# zilla1.net
KiCad netlist of a schematic drawn in EAGLE
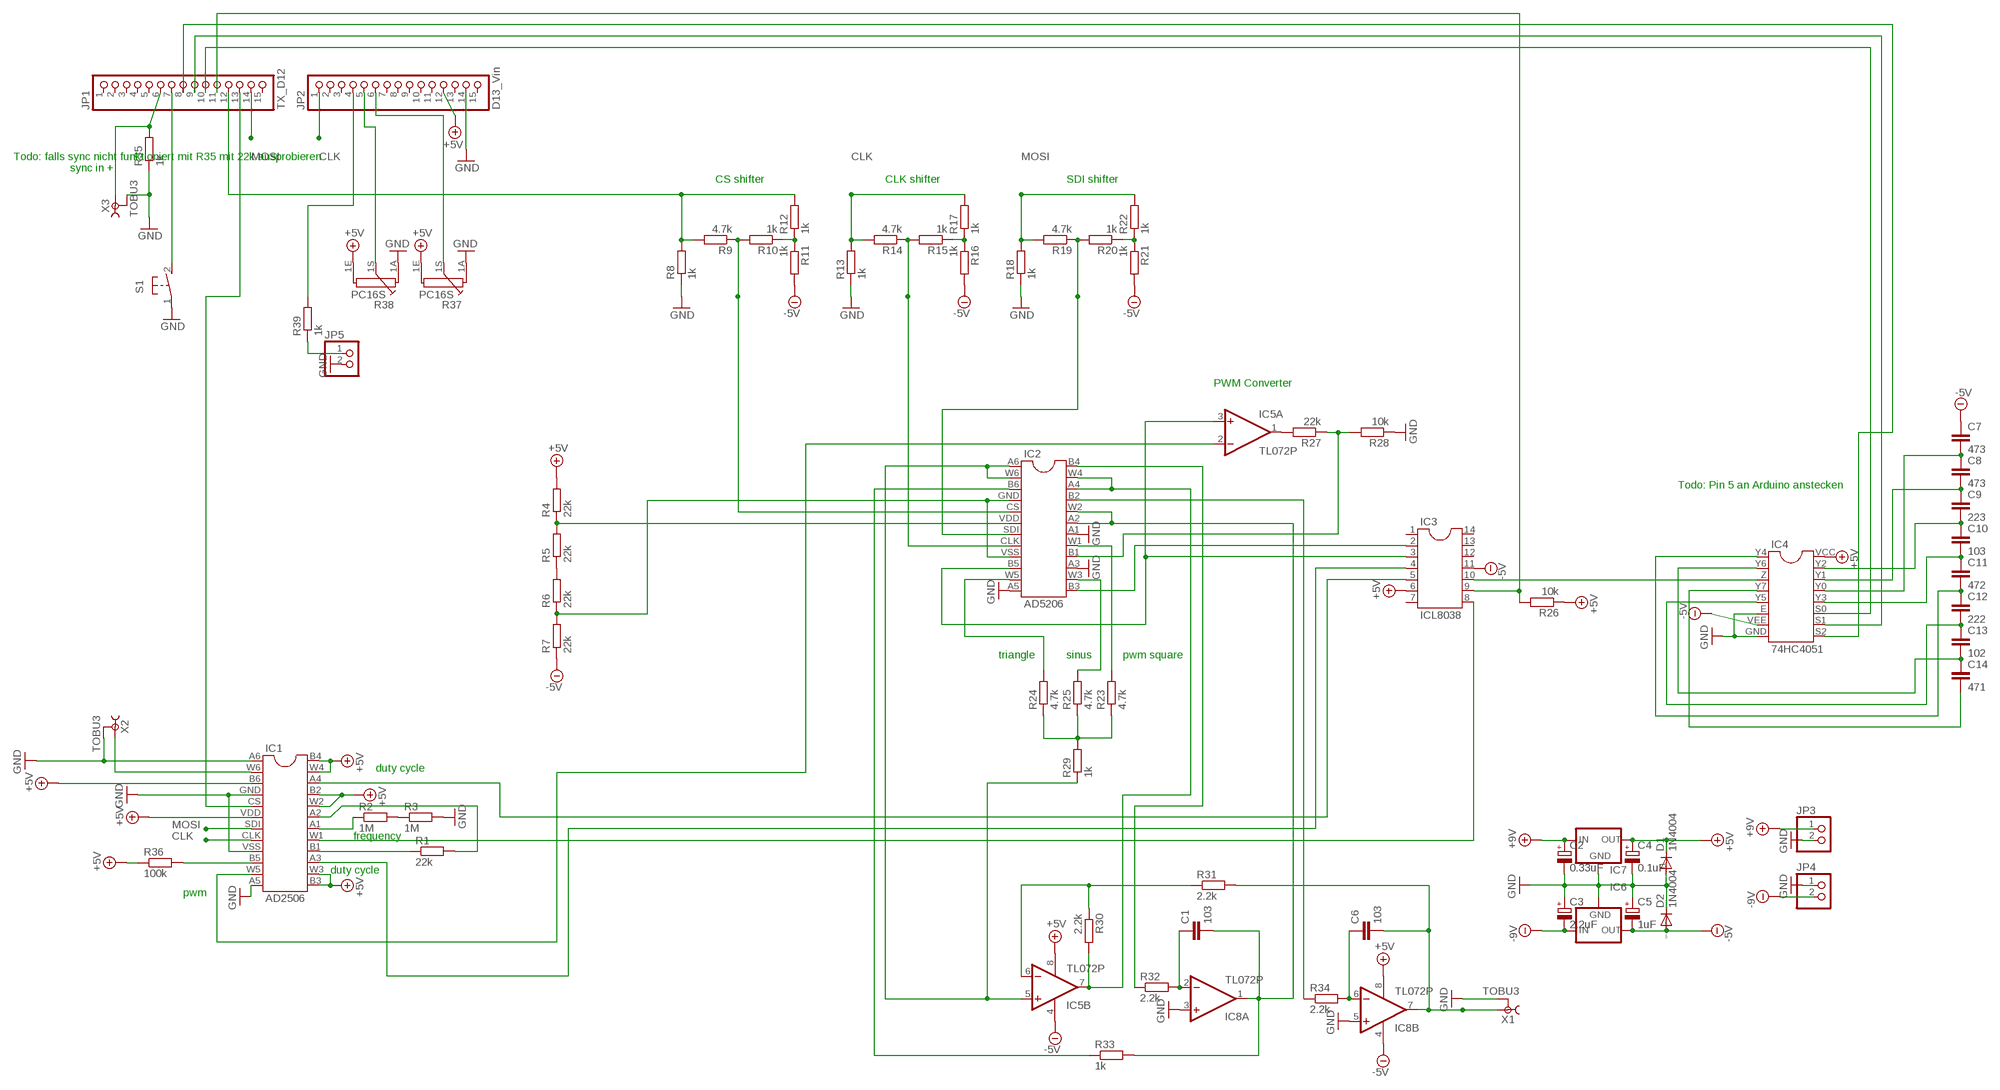
[diagram p0: schematic, sheet 1]

(export (version "E")
  (design (tool "Eeschema 10.0.6"))
  (components
    (comp (ref "C1")
      (value "103")
      (footprint "eagle-import:C025-024X044")
      (libsource (lib "eagle-import") (part "C-EU025-024X044"))
    )
    (comp (ref "C2")
      (value "0.33uF")
      (footprint "eagle-import:E2-5")
      (libsource (lib "eagle-import") (part "CPOL-EUE2-5"))
    )
    (comp (ref "C3")
      (value "2.2uF")
      (footprint "eagle-import:E2-5")
      (libsource (lib "eagle-import") (part "CPOL-EUE2-5"))
    )
    (comp (ref "C4")
      (value "0.1uF")
      (footprint "eagle-import:E2-5")
      (libsource (lib "eagle-import") (part "CPOL-EUE2-5"))
    )
    (comp (ref "C5")
      (value "1uF")
      (footprint "eagle-import:E2-5")
      (libsource (lib "eagle-import") (part "CPOL-EUE2-5"))
    )
    (comp (ref "C6")
      (value "103")
      (footprint "eagle-import:C025-024X044")
      (libsource (lib "eagle-import") (part "C-EU025-024X044"))
    )
    (comp (ref "C7")
      (value "473")
      (footprint "eagle-import:C025-024X044")
      (libsource (lib "eagle-import") (part "C-EU025-024X044"))
    )
    (comp (ref "C8")
      (value "473")
      (footprint "eagle-import:C025-024X044")
      (libsource (lib "eagle-import") (part "C-EU025-024X044"))
    )
    (comp (ref "C9")
      (value "223")
      (footprint "eagle-import:C025-024X044")
      (libsource (lib "eagle-import") (part "C-EU025-024X044"))
    )
    (comp (ref "C10")
      (value "103")
      (footprint "eagle-import:C025-024X044")
      (libsource (lib "eagle-import") (part "C-EU025-024X044"))
    )
    (comp (ref "C11")
      (value "472")
      (footprint "eagle-import:C025-024X044")
      (libsource (lib "eagle-import") (part "C-EU025-024X044"))
    )
    (comp (ref "C12")
      (value "222")
      (footprint "eagle-import:C025-024X044")
      (libsource (lib "eagle-import") (part "C-EU025-024X044"))
    )
    (comp (ref "C13")
      (value "102")
      (footprint "eagle-import:C025-024X044")
      (libsource (lib "eagle-import") (part "C-EU025-024X044"))
    )
    (comp (ref "C14")
      (value "471")
      (footprint "eagle-import:C025-024X044")
      (libsource (lib "eagle-import") (part "C-EU025-024X044"))
    )
    (comp (ref "D1")
      (value "1N4004")
      (footprint "eagle-import:DO41-10")
      (libsource (lib "eagle-import") (part "1N4004"))
    )
    (comp (ref "D2")
      (value "1N4004")
      (footprint "eagle-import:DO41-10")
      (libsource (lib "eagle-import") (part "1N4004"))
    )
    (comp (ref "IC1")
      (value "AD2506")
      (footprint "eagle-import:AD5206")
      (libsource (lib "eagle-import") (part "DIL24-3"))
    )
    (comp (ref "IC2")
      (value "AD5206")
      (footprint "eagle-import:AD5206")
      (libsource (lib "eagle-import") (part "DIL24-3"))
    )
    (comp (ref "IC3")
      (value "ICL8038")
      (footprint "eagle-import:DIL14")
      (libsource (lib "eagle-import") (part "DIL14"))
    )
    (comp (ref "IC4")
      (value "74HC4051")
      (footprint "eagle-import:DIL16")
      (libsource (lib "eagle-import") (part "DIL16"))
    )
    (comp (ref "IC5")
      (value "TL072P")
      (footprint "eagle-import:DIL08")
      (libsource (lib "eagle-import") (part "TL072P"))
    )
    (comp (ref "IC6")
      (value "79XXS")
      (footprint "eagle-import:79XXS")
      (libsource (lib "eagle-import") (part "79XXS"))
    )
    (comp (ref "IC7")
      (value "78XXS")
      (footprint "eagle-import:78XXS")
      (libsource (lib "eagle-import") (part "78XXS"))
    )
    (comp (ref "IC8")
      (value "TL072P")
      (footprint "eagle-import:DIL08")
      (libsource (lib "eagle-import") (part "TL072P"))
    )
    (comp (ref "JP1")
      (value "TX_D12")
      (footprint "eagle-import:1X15")
      (libsource (lib "eagle-import") (part "PINHD-1X15"))
    )
    (comp (ref "JP2")
      (value "D13_Vin")
      (footprint "eagle-import:1X15")
      (libsource (lib "eagle-import") (part "PINHD-1X15"))
    )
    (comp (ref "JP3")
      (value "PINHD-1X2")
      (footprint "eagle-import:1X02")
      (libsource (lib "eagle-import") (part "PINHD-1X2"))
    )
    (comp (ref "JP4")
      (value "PINHD-1X2")
      (footprint "eagle-import:1X02")
      (libsource (lib "eagle-import") (part "PINHD-1X2"))
    )
    (comp (ref "JP5")
      (value "PINHD-1X2")
      (footprint "eagle-import:1X02")
      (libsource (lib "eagle-import") (part "PINHD-1X2"))
    )
    (comp (ref "R1")
      (value "22k")
      (footprint "eagle-import:0207_7")
      (libsource (lib "eagle-import") (part "R-EU_0207/7"))
    )
    (comp (ref "R2")
      (value "1M")
      (footprint "eagle-import:0207_7")
      (libsource (lib "eagle-import") (part "R-EU_0207/7"))
    )
    (comp (ref "R3")
      (value "1M")
      (footprint "eagle-import:0207_7")
      (libsource (lib "eagle-import") (part "R-EU_0207/7"))
    )
    (comp (ref "R4")
      (value "22k")
      (footprint "eagle-import:0207_7")
      (libsource (lib "eagle-import") (part "R-EU_0207/7"))
    )
    (comp (ref "R5")
      (value "22k")
      (footprint "eagle-import:0207_7")
      (libsource (lib "eagle-import") (part "R-EU_0207/7"))
    )
    (comp (ref "R6")
      (value "22k")
      (footprint "eagle-import:0207_7")
      (libsource (lib "eagle-import") (part "R-EU_0207/7"))
    )
    (comp (ref "R7")
      (value "22k")
      (footprint "eagle-import:0207_7")
      (libsource (lib "eagle-import") (part "R-EU_0207/7"))
    )
    (comp (ref "R8")
      (value "1k")
      (footprint "eagle-import:0207_7")
      (libsource (lib "eagle-import") (part "R-EU_0207/7"))
    )
    (comp (ref "R9")
      (value "4.7k")
      (footprint "eagle-import:0207_7")
      (libsource (lib "eagle-import") (part "R-EU_0207/7"))
    )
    (comp (ref "R10")
      (value "1k")
      (footprint "eagle-import:0207_7")
      (libsource (lib "eagle-import") (part "R-EU_0207/7"))
    )
    (comp (ref "R11")
      (value "1k")
      (footprint "eagle-import:0207_7")
      (libsource (lib "eagle-import") (part "R-EU_0207/7"))
    )
    (comp (ref "R12")
      (value "1k")
      (footprint "eagle-import:0207_7")
      (libsource (lib "eagle-import") (part "R-EU_0207/7"))
    )
    (comp (ref "R13")
      (value "1k")
      (footprint "eagle-import:0207_7")
      (libsource (lib "eagle-import") (part "R-EU_0207/7"))
    )
    (comp (ref "R14")
      (value "4.7k")
      (footprint "eagle-import:0207_7")
      (libsource (lib "eagle-import") (part "R-EU_0207/7"))
    )
    (comp (ref "R15")
      (value "1k")
      (footprint "eagle-import:0207_7")
      (libsource (lib "eagle-import") (part "R-EU_0207/7"))
    )
    (comp (ref "R16")
      (value "1k")
      (footprint "eagle-import:0207_7")
      (libsource (lib "eagle-import") (part "R-EU_0207/7"))
    )
    (comp (ref "R17")
      (value "1k")
      (footprint "eagle-import:0207_7")
      (libsource (lib "eagle-import") (part "R-EU_0207/7"))
    )
    (comp (ref "R18")
      (value "1k")
      (footprint "eagle-import:0207_7")
      (libsource (lib "eagle-import") (part "R-EU_0207/7"))
    )
    (comp (ref "R19")
      (value "4.7k")
      (footprint "eagle-import:0207_7")
      (libsource (lib "eagle-import") (part "R-EU_0207/7"))
    )
    (comp (ref "R20")
      (value "1k")
      (footprint "eagle-import:0207_7")
      (libsource (lib "eagle-import") (part "R-EU_0207/7"))
    )
    (comp (ref "R21")
      (value "1k")
      (footprint "eagle-import:0207_7")
      (libsource (lib "eagle-import") (part "R-EU_0207/7"))
    )
    (comp (ref "R22")
      (value "1k")
      (footprint "eagle-import:0207_7")
      (libsource (lib "eagle-import") (part "R-EU_0207/7"))
    )
    (comp (ref "R23")
      (value "4.7k")
      (footprint "eagle-import:0207_7")
      (libsource (lib "eagle-import") (part "R-EU_0207/7"))
    )
    (comp (ref "R24")
      (value "4.7k")
      (footprint "eagle-import:0207_7")
      (libsource (lib "eagle-import") (part "R-EU_0207/7"))
    )
    (comp (ref "R25")
      (value "4.7k")
      (footprint "eagle-import:0207_7")
      (libsource (lib "eagle-import") (part "R-EU_0207/7"))
    )
    (comp (ref "R26")
      (value "10k")
      (footprint "eagle-import:0207_7")
      (libsource (lib "eagle-import") (part "R-EU_0207/7"))
    )
    (comp (ref "R27")
      (value "22k")
      (footprint "eagle-import:0207_7")
      (libsource (lib "eagle-import") (part "R-EU_0207/7"))
    )
    (comp (ref "R28")
      (value "10k")
      (footprint "eagle-import:0207_7")
      (libsource (lib "eagle-import") (part "R-EU_0207/7"))
    )
    (comp (ref "R29")
      (value "1k")
      (footprint "eagle-import:0207_7")
      (libsource (lib "eagle-import") (part "R-EU_0207/7"))
    )
    (comp (ref "R30")
      (value "2.2k")
      (footprint "eagle-import:0207_7")
      (libsource (lib "eagle-import") (part "R-EU_0207/7"))
    )
    (comp (ref "R31")
      (value "2.2k")
      (footprint "eagle-import:0207_7")
      (libsource (lib "eagle-import") (part "R-EU_0207/7"))
    )
    (comp (ref "R32")
      (value "2.2k")
      (footprint "eagle-import:0207_7")
      (libsource (lib "eagle-import") (part "R-EU_0207/7"))
    )
    (comp (ref "R33")
      (value "1k")
      (footprint "eagle-import:0207_7")
      (libsource (lib "eagle-import") (part "R-EU_0207/7"))
    )
    (comp (ref "R34")
      (value "2.2k")
      (footprint "eagle-import:0207_7")
      (libsource (lib "eagle-import") (part "R-EU_0207/7"))
    )
    (comp (ref "R35")
      (value "1k")
      (footprint "eagle-import:0207_7")
      (libsource (lib "eagle-import") (part "R-EU_0207/7"))
    )
    (comp (ref "R36")
      (value "100k")
      (footprint "eagle-import:0207_7")
      (libsource (lib "eagle-import") (part "R-EU_0207/7"))
    )
    (comp (ref "R37")
      (value "PC16S")
      (footprint "eagle-import:PC16S")
      (libsource (lib "eagle-import") (part "PC16S"))
    )
    (comp (ref "R38")
      (value "PC16S")
      (footprint "eagle-import:PC16S")
      (libsource (lib "eagle-import") (part "PC16S"))
    )
    (comp (ref "R39")
      (value "1k")
      (footprint "eagle-import:0207_7")
      (libsource (lib "eagle-import") (part "R-EU_0207/7"))
    )
    (comp (ref "S1")
      (value "31-XX")
      (footprint "eagle-import:B3F-31XX")
      (fields (field (name "MPN") "B3F-3100"))
      (libsource (lib "eagle-import") (part "31-XX"))
    )
    (comp (ref "X1")
      (value "TOBU3")
      (footprint "eagle-import:TOBU3")
      (fields (field (name "MF") "FARNELL") (field (name "MPN") "TOBU 3"))
      (libsource (lib "eagle-import") (part "TOBU3"))
    )
    (comp (ref "X2")
      (value "TOBU3")
      (footprint "eagle-import:TOBU3")
      (fields (field (name "MF") "FARNELL") (field (name "MPN") "TOBU 3"))
      (libsource (lib "eagle-import") (part "TOBU3"))
    )
    (comp (ref "X3")
      (value "TOBU3")
      (footprint "eagle-import:TOBU3")
      (fields (field (name "MF") "FARNELL") (field (name "MPN") "TOBU 3"))
      (libsource (lib "eagle-import") (part "TOBU3"))
    )
  )
  (nets
    (net (code "1") (name "+5V") (class "Default")
      (node (ref "C4") (pin "+") (pinfunction "+_+") (pintype "passive"))
      (node (ref "D1") (pin "C") (pinfunction "C_C") (pintype "passive"))
      (node (ref "IC1") (pin "B2") (pinfunction "21_B2") (pintype "passive"))
      (node (ref "IC1") (pin "B3") (pinfunction "13_B3") (pintype "passive"))
      (node (ref "IC1") (pin "B4") (pinfunction "24_B4") (pintype "passive"))
      (node (ref "IC1") (pin "B6") (pinfunction "3_B6") (pintype "passive"))
      (node (ref "IC1") (pin "VDD") (pinfunction "6_VDD") (pintype "passive"))
      (node (ref "IC1") (pin "W2") (pinfunction "20_W2") (pintype "passive"))
      (node (ref "IC1") (pin "W3") (pinfunction "14_W3") (pintype "passive"))
      (node (ref "IC1") (pin "W4") (pinfunction "23_W4") (pintype "passive"))
      (node (ref "IC3") (pin "6") (pinfunction "6_6") (pintype "passive"))
      (node (ref "IC4") (pin "VCC") (pinfunction "16_VCC") (pintype "passive"))
      (node (ref "IC5") (pin "8") (pinfunction "V+_8") (pintype "power_in"))
      (node (ref "IC7") (pin "OUT") (pinfunction "OUT_OUT") (pintype "passive"))
      (node (ref "IC8") (pin "8") (pinfunction "V+_8") (pintype "power_in"))
      (node (ref "JP2") (pin "12") (pinfunction "12_12") (pintype "passive"))
      (node (ref "R26") (pin "1") (pinfunction "1_1") (pintype "passive"))
      (node (ref "R36") (pin "1") (pinfunction "1_1") (pintype "passive"))
      (node (ref "R37") (pin "1E") (pinfunction "1E_1E") (pintype "passive"))
      (node (ref "R38") (pin "1E") (pinfunction "1E_1E") (pintype "passive"))
      (node (ref "R4") (pin "2") (pinfunction "2_2") (pintype "passive"))
    )
    (net (code "2") (name "+9V") (class "Default")
      (node (ref "C2") (pin "+") (pinfunction "+_+") (pintype "passive"))
      (node (ref "IC7") (pin "IN") (pinfunction "IN_IN") (pintype "input"))
      (node (ref "JP3") (pin "1") (pinfunction "1_1") (pintype "passive"))
    )
    (net (code "3") (name "-5V") (class "Default")
      (node (ref "C5") (pin "-") (pinfunction "-_-") (pintype "passive"))
      (node (ref "C7") (pin "1") (pinfunction "1_1") (pintype "passive"))
      (node (ref "D2") (pin "A") (pinfunction "A_A") (pintype "passive"))
      (node (ref "IC3") (pin "11") (pinfunction "11_11") (pintype "passive"))
      (node (ref "IC4") (pin "VEE") (pinfunction "7_VEE") (pintype "passive"))
      (node (ref "IC5") (pin "4") (pinfunction "V-_4") (pintype "power_in"))
      (node (ref "IC6") (pin "OUT") (pinfunction "OUT_OUT") (pintype "passive"))
      (node (ref "IC8") (pin "4") (pinfunction "V-_4") (pintype "power_in"))
      (node (ref "R11") (pin "2") (pinfunction "2_2") (pintype "passive"))
      (node (ref "R16") (pin "2") (pinfunction "2_2") (pintype "passive"))
      (node (ref "R21") (pin "2") (pinfunction "2_2") (pintype "passive"))
      (node (ref "R7") (pin "1") (pinfunction "1_1") (pintype "passive"))
    )
    (net (code "4") (name "-9V") (class "Default")
      (node (ref "C3") (pin "-") (pinfunction "-_-") (pintype "passive"))
      (node (ref "IC6") (pin "IN") (pinfunction "IN_IN") (pintype "input"))
      (node (ref "JP4") (pin "2") (pinfunction "2_2") (pintype "passive"))
    )
    (net (code "5") (name "/CLK") (class "Default")
      (node (ref "IC1") (pin "CLK") (pinfunction "8_CLK") (pintype "passive"))
      (node (ref "JP2") (pin "1") (pinfunction "1_1") (pintype "passive"))
      (node (ref "R13") (pin "2") (pinfunction "2_2") (pintype "passive"))
      (node (ref "R14") (pin "2") (pinfunction "2_2") (pintype "passive"))
      (node (ref "R17") (pin "2") (pinfunction "2_2") (pintype "passive"))
    )
    (net (code "6") (name "/MOSI") (class "Default")
      (node (ref "IC1") (pin "SDI") (pinfunction "7_SDI") (pintype "passive"))
      (node (ref "JP1") (pin "14") (pinfunction "14_14") (pintype "passive"))
      (node (ref "R18") (pin "2") (pinfunction "2_2") (pintype "passive"))
      (node (ref "R19") (pin "2") (pinfunction "2_2") (pintype "passive"))
      (node (ref "R22") (pin "2") (pinfunction "2_2") (pintype "passive"))
    )
    (net (code "7") (name "GND") (class "Default")
      (node (ref "C2") (pin "-") (pinfunction "-_-") (pintype "passive"))
      (node (ref "C3") (pin "+") (pinfunction "+_+") (pintype "passive"))
      (node (ref "C4") (pin "-") (pinfunction "-_-") (pintype "passive"))
      (node (ref "C5") (pin "+") (pinfunction "+_+") (pintype "passive"))
      (node (ref "D1") (pin "A") (pinfunction "A_A") (pintype "passive"))
      (node (ref "D2") (pin "C") (pinfunction "C_C") (pintype "passive"))
      (node (ref "IC1") (pin "A5") (pinfunction "12_A5") (pintype "passive"))
      (node (ref "IC1") (pin "A6") (pinfunction "TEST_A6") (pintype "passive"))
      (node (ref "IC1") (pin "GND") (pinfunction "4_GND") (pintype "passive"))
      (node (ref "IC1") (pin "VSS") (pinfunction "9_VSS") (pintype "passive"))
      (node (ref "IC2") (pin "A1") (pinfunction "18_A1") (pintype "passive"))
      (node (ref "IC2") (pin "A3") (pinfunction "15_A3") (pintype "passive"))
      (node (ref "IC2") (pin "A5") (pinfunction "12_A5") (pintype "passive"))
      (node (ref "IC4") (pin "E") (pinfunction "6_E") (pintype "passive"))
      (node (ref "IC4") (pin "GND") (pinfunction "8_GND") (pintype "passive"))
      (node (ref "IC6") (pin "GND") (pinfunction "GND_GND") (pintype "input"))
      (node (ref "IC7") (pin "GND") (pinfunction "GND_GND") (pintype "input"))
      (node (ref "IC8") (pin "3") (pinfunction "+IN_3") (pintype "input"))
      (node (ref "IC8") (pin "5") (pinfunction "+IN_5") (pintype "input"))
      (node (ref "JP2") (pin "14") (pinfunction "14_14") (pintype "passive"))
      (node (ref "JP3") (pin "2") (pinfunction "2_2") (pintype "passive"))
      (node (ref "JP4") (pin "1") (pinfunction "1_1") (pintype "passive"))
      (node (ref "JP5") (pin "2") (pinfunction "2_2") (pintype "passive"))
      (node (ref "R13") (pin "1") (pinfunction "1_1") (pintype "passive"))
      (node (ref "R18") (pin "1") (pinfunction "1_1") (pintype "passive"))
      (node (ref "R28") (pin "1") (pinfunction "1_1") (pintype "passive"))
      (node (ref "R3") (pin "2") (pinfunction "2_2") (pintype "passive"))
      (node (ref "R35") (pin "1") (pinfunction "1_1") (pintype "passive"))
      (node (ref "R37") (pin "1A") (pinfunction "1A_1A") (pintype "passive"))
      (node (ref "R38") (pin "1A") (pinfunction "1A_1A") (pintype "passive"))
      (node (ref "R8") (pin "1") (pinfunction "1_1") (pintype "passive"))
      (node (ref "S1") (pin "1") (pinfunction "P_1") (pintype "passive"))
      (node (ref "X1") (pin "2") (pinfunction "2_2") (pintype "passive"))
      (node (ref "X1") (pin "2@1") (pinfunction "2_2@1") (pintype "passive"))
      (node (ref "X1") (pin "2@2") (pinfunction "2_2@2") (pintype "passive"))
      (node (ref "X2") (pin "2") (pinfunction "2_2") (pintype "passive"))
      (node (ref "X2") (pin "2@1") (pinfunction "2_2@1") (pintype "passive"))
      (node (ref "X2") (pin "2@2") (pinfunction "2_2@2") (pintype "passive"))
      (node (ref "X3") (pin "2") (pinfunction "2_2") (pintype "passive"))
      (node (ref "X3") (pin "2@1") (pinfunction "2_2@1") (pintype "passive"))
      (node (ref "X3") (pin "2@2") (pinfunction "2_2@2") (pintype "passive"))
    )
    (net (code "8") (name "Net-(IC1-5)") (class "Default")
      (node (ref "IC1") (pin "CS") (pinfunction "5_CS") (pintype "passive"))
      (node (ref "JP1") (pin "13") (pinfunction "13_13") (pintype "passive"))
    )
    (net (code "9") (name "Net-(IC1-10)") (class "Default")
      (node (ref "IC1") (pin "B5") (pinfunction "10_B5") (pintype "passive"))
      (node (ref "R36") (pin "2") (pinfunction "2_2") (pintype "passive"))
    )
    (net (code "10") (name "Net-(IC1-11)") (class "Default")
      (node (ref "IC1") (pin "W5") (pinfunction "11_W5") (pintype "passive"))
      (node (ref "IC5") (pin "2") (pinfunction "-IN_2") (pintype "input"))
    )
    (net (code "11") (name "Net-(IC1-15)") (class "Default")
      (node (ref "IC1") (pin "A3") (pinfunction "15_A3") (pintype "passive"))
      (node (ref "IC3") (pin "4") (pinfunction "4_4") (pintype "passive"))
    )
    (net (code "12") (name "Net-(IC1-16)") (class "Default")
      (node (ref "IC1") (pin "B1") (pinfunction "16_B1") (pintype "passive"))
      (node (ref "R1") (pin "1") (pinfunction "1_1") (pintype "passive"))
    )
    (net (code "13") (name "Net-(IC1-17)") (class "Default")
      (node (ref "IC1") (pin "W1") (pinfunction "17_W1") (pintype "passive"))
      (node (ref "IC3") (pin "8") (pinfunction "8_8") (pintype "passive"))
    )
    (net (code "14") (name "Net-(IC1-18)") (class "Default")
      (node (ref "IC1") (pin "A1") (pinfunction "18_A1") (pintype "passive"))
      (node (ref "R2") (pin "1") (pinfunction "1_1") (pintype "passive"))
    )
    (net (code "15") (name "Net-(IC1-19)") (class "Default")
      (node (ref "IC1") (pin "A2") (pinfunction "19_A2") (pintype "passive"))
      (node (ref "R1") (pin "2") (pinfunction "2_2") (pintype "passive"))
    )
    (net (code "16") (name "Net-(IC1-22)") (class "Default")
      (node (ref "IC1") (pin "A4") (pinfunction "22_A4") (pintype "passive"))
      (node (ref "IC3") (pin "5") (pinfunction "5_5") (pintype "passive"))
    )
    (net (code "17") (name "Net-(IC1-VCC)") (class "Default")
      (node (ref "IC1") (pin "W6") (pinfunction "VCC_W6") (pintype "passive"))
      (node (ref "X2") (pin "1") (pinfunction "1_1") (pintype "passive"))
    )
    (net (code "18") (name "Net-(IC2-3)") (class "Default")
      (node (ref "IC2") (pin "B6") (pinfunction "3_B6") (pintype "passive"))
      (node (ref "R33") (pin "1") (pinfunction "1_1") (pintype "passive"))
    )
    (net (code "19") (name "Net-(IC2-4)") (class "Default")
      (node (ref "IC2") (pin "GND") (pinfunction "4_GND") (pintype "passive"))
      (node (ref "IC2") (pin "VSS") (pinfunction "9_VSS") (pintype "passive"))
      (node (ref "R6") (pin "1") (pinfunction "1_1") (pintype "passive"))
      (node (ref "R7") (pin "2") (pinfunction "2_2") (pintype "passive"))
    )
    (net (code "20") (name "Net-(IC2-5)") (class "Default")
      (node (ref "IC2") (pin "CS") (pinfunction "5_CS") (pintype "passive"))
      (node (ref "R10") (pin "2") (pinfunction "2_2") (pintype "passive"))
      (node (ref "R9") (pin "1") (pinfunction "1_1") (pintype "passive"))
    )
    (net (code "21") (name "Net-(IC2-6)") (class "Default")
      (node (ref "IC2") (pin "VDD") (pinfunction "6_VDD") (pintype "passive"))
      (node (ref "R4") (pin "1") (pinfunction "1_1") (pintype "passive"))
      (node (ref "R5") (pin "2") (pinfunction "2_2") (pintype "passive"))
    )
    (net (code "22") (name "Net-(IC2-7)") (class "Default")
      (node (ref "IC2") (pin "SDI") (pinfunction "7_SDI") (pintype "passive"))
      (node (ref "R19") (pin "1") (pinfunction "1_1") (pintype "passive"))
      (node (ref "R20") (pin "2") (pinfunction "2_2") (pintype "passive"))
    )
    (net (code "23") (name "Net-(IC2-8)") (class "Default")
      (node (ref "IC2") (pin "CLK") (pinfunction "8_CLK") (pintype "passive"))
      (node (ref "R14") (pin "1") (pinfunction "1_1") (pintype "passive"))
      (node (ref "R15") (pin "2") (pinfunction "2_2") (pintype "passive"))
    )
    (net (code "24") (name "Net-(IC2-10)") (class "Default")
      (node (ref "IC2") (pin "B5") (pinfunction "10_B5") (pintype "passive"))
      (node (ref "IC3") (pin "3") (pinfunction "3_3") (pintype "passive"))
      (node (ref "IC5") (pin "3") (pinfunction "+IN_3") (pintype "input"))
    )
    (net (code "25") (name "Net-(IC2-11)") (class "Default")
      (node (ref "IC2") (pin "W5") (pinfunction "11_W5") (pintype "passive"))
      (node (ref "R24") (pin "2") (pinfunction "2_2") (pintype "passive"))
    )
    (net (code "26") (name "Net-(IC2-13)") (class "Default")
      (node (ref "IC2") (pin "B3") (pinfunction "13_B3") (pintype "passive"))
      (node (ref "IC3") (pin "2") (pinfunction "2_2") (pintype "passive"))
    )
    (net (code "27") (name "Net-(IC2-14)") (class "Default")
      (node (ref "IC2") (pin "W3") (pinfunction "14_W3") (pintype "passive"))
      (node (ref "R25") (pin "2") (pinfunction "2_2") (pintype "passive"))
    )
    (net (code "28") (name "Net-(IC2-16)") (class "Default")
      (node (ref "IC2") (pin "B1") (pinfunction "16_B1") (pintype "passive"))
      (node (ref "R27") (pin "1") (pinfunction "1_1") (pintype "passive"))
      (node (ref "R28") (pin "2") (pinfunction "2_2") (pintype "passive"))
    )
    (net (code "29") (name "Net-(IC2-17)") (class "Default")
      (node (ref "IC2") (pin "W1") (pinfunction "17_W1") (pintype "passive"))
      (node (ref "R23") (pin "2") (pinfunction "2_2") (pintype "passive"))
    )
    (net (code "30") (name "Net-(IC2-19)") (class "Default")
      (node (ref "C1") (pin "2") (pinfunction "2_2") (pintype "passive"))
      (node (ref "IC2") (pin "A2") (pinfunction "19_A2") (pintype "passive"))
      (node (ref "IC2") (pin "W2") (pinfunction "20_W2") (pintype "passive"))
      (node (ref "IC8") (pin "1") (pinfunction "OUT_1") (pintype "output"))
      (node (ref "R33") (pin "2") (pinfunction "2_2") (pintype "passive"))
    )
    (net (code "31") (name "Net-(IC2-21)") (class "Default")
      (node (ref "IC2") (pin "B2") (pinfunction "21_B2") (pintype "passive"))
      (node (ref "R34") (pin "1") (pinfunction "1_1") (pintype "passive"))
    )
    (net (code "32") (name "Net-(IC2-22)") (class "Default")
      (node (ref "IC2") (pin "A4") (pinfunction "22_A4") (pintype "passive"))
      (node (ref "IC2") (pin "W4") (pinfunction "23_W4") (pintype "passive"))
      (node (ref "IC5") (pin "7") (pinfunction "OUT_7") (pintype "output"))
      (node (ref "R30") (pin "2") (pinfunction "2_2") (pintype "passive"))
    )
    (net (code "33") (name "Net-(IC2-24)") (class "Default")
      (node (ref "IC2") (pin "B4") (pinfunction "24_B4") (pintype "passive"))
      (node (ref "R32") (pin "1") (pinfunction "1_1") (pintype "passive"))
    )
    (net (code "34") (name "Net-(IC2-TEST)") (class "Default")
      (node (ref "IC2") (pin "A6") (pinfunction "TEST_A6") (pintype "passive"))
      (node (ref "IC2") (pin "W6") (pinfunction "VCC_W6") (pintype "passive"))
      (node (ref "IC5") (pin "5") (pinfunction "+IN_5") (pintype "input"))
      (node (ref "R29") (pin "1") (pinfunction "1_1") (pintype "passive"))
    )
    (net (code "35") (name "Net-(IC3-Pad9)") (class "Default")
      (node (ref "IC3") (pin "9") (pinfunction "9_9") (pintype "passive"))
      (node (ref "JP1") (pin "11") (pinfunction "11_11") (pintype "passive"))
      (node (ref "R26") (pin "2") (pinfunction "2_2") (pintype "passive"))
    )
    (net (code "36") (name "Net-(IC4-1)") (class "Default")
      (node (ref "C11") (pin "2") (pinfunction "2_2") (pintype "passive"))
      (node (ref "C12") (pin "1") (pinfunction "1_1") (pintype "passive"))
      (node (ref "IC4") (pin "Y4") (pinfunction "1_Y4") (pintype "passive"))
    )
    (net (code "37") (name "Net-(IC4-2)") (class "Default")
      (node (ref "C13") (pin "2") (pinfunction "2_2") (pintype "passive"))
      (node (ref "C14") (pin "1") (pinfunction "1_1") (pintype "passive"))
      (node (ref "IC4") (pin "Y6") (pinfunction "2_Y6") (pintype "passive"))
    )
    (net (code "38") (name "Net-(IC4-3)") (class "Default")
      (node (ref "IC3") (pin "10") (pinfunction "10_10") (pintype "passive"))
      (node (ref "IC4") (pin "Z") (pinfunction "3_Z") (pintype "passive"))
    )
    (net (code "39") (name "Net-(IC4-4)") (class "Default")
      (node (ref "C14") (pin "2") (pinfunction "2_2") (pintype "passive"))
      (node (ref "IC4") (pin "Y7") (pinfunction "4_Y7") (pintype "passive"))
    )
    (net (code "40") (name "Net-(IC4-5)") (class "Default")
      (node (ref "C12") (pin "2") (pinfunction "2_2") (pintype "passive"))
      (node (ref "C13") (pin "1") (pinfunction "1_1") (pintype "passive"))
      (node (ref "IC4") (pin "Y5") (pinfunction "5_Y5") (pintype "passive"))
    )
    (net (code "41") (name "Net-(IC4-9)") (class "Default")
      (node (ref "IC4") (pin "S2") (pinfunction "9_S2") (pintype "passive"))
      (node (ref "JP1") (pin "8") (pinfunction "8_8") (pintype "passive"))
    )
    (net (code "42") (name "Net-(IC4-10)") (class "Default")
      (node (ref "IC4") (pin "S1") (pinfunction "10_S1") (pintype "passive"))
      (node (ref "JP1") (pin "9") (pinfunction "9_9") (pintype "passive"))
    )
    (net (code "43") (name "Net-(IC4-11)") (class "Default")
      (node (ref "IC4") (pin "S0") (pinfunction "11_S0") (pintype "passive"))
      (node (ref "JP1") (pin "10") (pinfunction "10_10") (pintype "passive"))
    )
    (net (code "44") (name "Net-(IC4-12)") (class "Default")
      (node (ref "C10") (pin "2") (pinfunction "2_2") (pintype "passive"))
      (node (ref "C11") (pin "1") (pinfunction "1_1") (pintype "passive"))
      (node (ref "IC4") (pin "Y3") (pinfunction "12_Y3") (pintype "passive"))
    )
    (net (code "45") (name "Net-(IC4-13)") (class "Default")
      (node (ref "C7") (pin "2") (pinfunction "2_2") (pintype "passive"))
      (node (ref "C8") (pin "1") (pinfunction "1_1") (pintype "passive"))
      (node (ref "IC4") (pin "Y0") (pinfunction "13_Y0") (pintype "passive"))
    )
    (net (code "46") (name "Net-(IC4-14)") (class "Default")
      (node (ref "C8") (pin "2") (pinfunction "2_2") (pintype "passive"))
      (node (ref "C9") (pin "1") (pinfunction "1_1") (pintype "passive"))
      (node (ref "IC4") (pin "Y1") (pinfunction "14_Y1") (pintype "passive"))
    )
    (net (code "47") (name "Net-(IC4-15)") (class "Default")
      (node (ref "C10") (pin "1") (pinfunction "1_1") (pintype "passive"))
      (node (ref "C9") (pin "2") (pinfunction "2_2") (pintype "passive"))
      (node (ref "IC4") (pin "Y2") (pinfunction "15_Y2") (pintype "passive"))
    )
    (net (code "48") (name "Net-(IC5A-OUT)") (class "Default")
      (node (ref "IC5") (pin "1") (pinfunction "OUT_1") (pintype "output"))
      (node (ref "R27") (pin "2") (pinfunction "2_2") (pintype "passive"))
    )
    (net (code "49") (name "Net-(IC5B--IN)") (class "Default")
      (node (ref "IC5") (pin "6") (pinfunction "-IN_6") (pintype "input"))
      (node (ref "R30") (pin "1") (pinfunction "1_1") (pintype "passive"))
      (node (ref "R31") (pin "1") (pinfunction "1_1") (pintype "passive"))
    )
    (net (code "50") (name "Net-(IC8A--IN)") (class "Default")
      (node (ref "C1") (pin "1") (pinfunction "1_1") (pintype "passive"))
      (node (ref "IC8") (pin "2") (pinfunction "-IN_2") (pintype "input"))
      (node (ref "R32") (pin "2") (pinfunction "2_2") (pintype "passive"))
    )
    (net (code "51") (name "Net-(IC8B--IN)") (class "Default")
      (node (ref "C6") (pin "1") (pinfunction "1_1") (pintype "passive"))
      (node (ref "IC8") (pin "6") (pinfunction "-IN_6") (pintype "input"))
      (node (ref "R34") (pin "2") (pinfunction "2_2") (pintype "passive"))
    )
    (net (code "52") (name "Net-(IC8B-OUT)") (class "Default")
      (node (ref "C6") (pin "2") (pinfunction "2_2") (pintype "passive"))
      (node (ref "IC8") (pin "7") (pinfunction "OUT_7") (pintype "output"))
      (node (ref "R31") (pin "2") (pinfunction "2_2") (pintype "passive"))
      (node (ref "X1") (pin "1") (pinfunction "1_1") (pintype "passive"))
    )
    (net (code "53") (name "Net-(JP1-Pad6)") (class "Default")
      (node (ref "JP1") (pin "6") (pinfunction "6_6") (pintype "passive"))
      (node (ref "R35") (pin "2") (pinfunction "2_2") (pintype "passive"))
      (node (ref "X3") (pin "1") (pinfunction "1_1") (pintype "passive"))
    )
    (net (code "54") (name "Net-(JP1-Pad12)") (class "Default")
      (node (ref "JP1") (pin "12") (pinfunction "12_12") (pintype "passive"))
      (node (ref "R12") (pin "2") (pinfunction "2_2") (pintype "passive"))
      (node (ref "R8") (pin "2") (pinfunction "2_2") (pintype "passive"))
      (node (ref "R9") (pin "2") (pinfunction "2_2") (pintype "passive"))
    )
    (net (code "55") (name "Net-(JP2-Pad4)") (class "Default")
      (node (ref "JP2") (pin "4") (pinfunction "4_4") (pintype "passive"))
      (node (ref "R39") (pin "2") (pinfunction "2_2") (pintype "passive"))
    )
    (net (code "56") (name "Net-(JP2-Pad5)") (class "Default")
      (node (ref "JP2") (pin "5") (pinfunction "5_5") (pintype "passive"))
      (node (ref "R38") (pin "1S") (pinfunction "1S_1S") (pintype "passive"))
    )
    (net (code "57") (name "Net-(JP2-Pad6)") (class "Default")
      (node (ref "JP2") (pin "6") (pinfunction "6_6") (pintype "passive"))
      (node (ref "R37") (pin "1S") (pinfunction "1S_1S") (pintype "passive"))
    )
    (net (code "58") (name "Net-(JP5-Pad1)") (class "Default")
      (node (ref "JP5") (pin "1") (pinfunction "1_1") (pintype "passive"))
      (node (ref "R39") (pin "1") (pinfunction "1_1") (pintype "passive"))
    )
    (net (code "59") (name "Net-(R2-Pad2)") (class "Default")
      (node (ref "R2") (pin "2") (pinfunction "2_2") (pintype "passive"))
      (node (ref "R3") (pin "1") (pinfunction "1_1") (pintype "passive"))
    )
    (net (code "60") (name "Net-(R5-Pad1)") (class "Default")
      (node (ref "R5") (pin "1") (pinfunction "1_1") (pintype "passive"))
      (node (ref "R6") (pin "2") (pinfunction "2_2") (pintype "passive"))
    )
    (net (code "61") (name "Net-(R10-Pad1)") (class "Default")
      (node (ref "R10") (pin "1") (pinfunction "1_1") (pintype "passive"))
      (node (ref "R11") (pin "1") (pinfunction "1_1") (pintype "passive"))
      (node (ref "R12") (pin "1") (pinfunction "1_1") (pintype "passive"))
    )
    (net (code "62") (name "Net-(R15-Pad1)") (class "Default")
      (node (ref "R15") (pin "1") (pinfunction "1_1") (pintype "passive"))
      (node (ref "R16") (pin "1") (pinfunction "1_1") (pintype "passive"))
      (node (ref "R17") (pin "1") (pinfunction "1_1") (pintype "passive"))
    )
    (net (code "63") (name "Net-(R20-Pad1)") (class "Default")
      (node (ref "R20") (pin "1") (pinfunction "1_1") (pintype "passive"))
      (node (ref "R21") (pin "1") (pinfunction "1_1") (pintype "passive"))
      (node (ref "R22") (pin "1") (pinfunction "1_1") (pintype "passive"))
    )
    (net (code "64") (name "Net-(R23-Pad1)") (class "Default")
      (node (ref "R23") (pin "1") (pinfunction "1_1") (pintype "passive"))
      (node (ref "R24") (pin "1") (pinfunction "1_1") (pintype "passive"))
      (node (ref "R25") (pin "1") (pinfunction "1_1") (pintype "passive"))
      (node (ref "R29") (pin "2") (pinfunction "2_2") (pintype "passive"))
    )
    (net (code "65") (name "Net-(S1-S)") (class "Default")
      (node (ref "JP1") (pin "7") (pinfunction "7_7") (pintype "passive"))
      (node (ref "S1") (pin "2") (pinfunction "S_2") (pintype "passive"))
    )
    (net (code "66") (name "unconnected-(IC3-Pad1)") (class "Default")
      (node (ref "IC3") (pin "1") (pinfunction "1_1") (pintype "passive"))
    )
    (net (code "67") (name "unconnected-(IC3-Pad7)") (class "Default")
      (node (ref "IC3") (pin "7") (pinfunction "7_7") (pintype "passive"))
    )
    (net (code "68") (name "unconnected-(IC3-Pad12)") (class "Default")
      (node (ref "IC3") (pin "12") (pinfunction "12_12") (pintype "passive"))
    )
    (net (code "69") (name "unconnected-(IC3-Pad13)") (class "Default")
      (node (ref "IC3") (pin "13") (pinfunction "13_13") (pintype "passive"))
    )
    (net (code "70") (name "unconnected-(IC3-Pad14)") (class "Default")
      (node (ref "IC3") (pin "14") (pinfunction "14_14") (pintype "passive"))
    )
    (net (code "71") (name "unconnected-(JP1-Pad1)") (class "Default")
      (node (ref "JP1") (pin "1") (pinfunction "1_1") (pintype "passive"))
    )
    (net (code "72") (name "unconnected-(JP1-Pad2)") (class "Default")
      (node (ref "JP1") (pin "2") (pinfunction "2_2") (pintype "passive"))
    )
    (net (code "73") (name "unconnected-(JP1-Pad3)") (class "Default")
      (node (ref "JP1") (pin "3") (pinfunction "3_3") (pintype "passive"))
    )
    (net (code "74") (name "unconnected-(JP1-Pad4)") (class "Default")
      (node (ref "JP1") (pin "4") (pinfunction "4_4") (pintype "passive"))
    )
    (net (code "75") (name "unconnected-(JP1-Pad5)") (class "Default")
      (node (ref "JP1") (pin "5") (pinfunction "5_5") (pintype "passive"))
    )
    (net (code "76") (name "unconnected-(JP1-Pad15)") (class "Default")
      (node (ref "JP1") (pin "15") (pinfunction "15_15") (pintype "passive"))
    )
    (net (code "77") (name "unconnected-(JP2-Pad2)") (class "Default")
      (node (ref "JP2") (pin "2") (pinfunction "2_2") (pintype "passive"))
    )
    (net (code "78") (name "unconnected-(JP2-Pad3)") (class "Default")
      (node (ref "JP2") (pin "3") (pinfunction "3_3") (pintype "passive"))
    )
    (net (code "79") (name "unconnected-(JP2-Pad7)") (class "Default")
      (node (ref "JP2") (pin "7") (pinfunction "7_7") (pintype "passive"))
    )
    (net (code "80") (name "unconnected-(JP2-Pad8)") (class "Default")
      (node (ref "JP2") (pin "8") (pinfunction "8_8") (pintype "passive"))
    )
    (net (code "81") (name "unconnected-(JP2-Pad9)") (class "Default")
      (node (ref "JP2") (pin "9") (pinfunction "9_9") (pintype "passive"))
    )
    (net (code "82") (name "unconnected-(JP2-Pad10)") (class "Default")
      (node (ref "JP2") (pin "10") (pinfunction "10_10") (pintype "passive"))
    )
    (net (code "83") (name "unconnected-(JP2-Pad11)") (class "Default")
      (node (ref "JP2") (pin "11") (pinfunction "11_11") (pintype "passive"))
    )
    (net (code "84") (name "unconnected-(JP2-Pad13)") (class "Default")
      (node (ref "JP2") (pin "13") (pinfunction "13_13") (pintype "passive"))
    )
    (net (code "85") (name "unconnected-(JP2-Pad15)") (class "Default")
      (node (ref "JP2") (pin "15") (pinfunction "15_15") (pintype "passive"))
    )
  )
)
